# LM60.net
KiCad netlist of a schematic drawn in Altium Designer
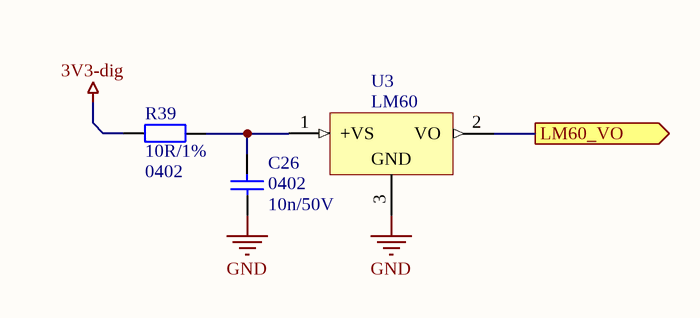
[diagram p0: LM60.SchDoc]

(export (version "E")
  (design (tool "Eeschema 10.0.6"))
  (components
    (comp (ref "C26")
      (value "10n/50V")
      (footprint "SMD_Capacitor_0402")
      (description "Ceramic Cap Murata Automotive 10n/50V X7R 0402")
      (fields
        (field (name "MANUFACTURER") "Murata")
        (field (name "MANUFACTURERPARTNUMBER") "GCM155R71H103KA55D")
        (field (name "PACKAGE") "0402")
      )
      (libsource (lib "capacitors") (part "Cer_GCM155R71H103KA55D"))
    )
    (comp (ref "R39")
      (value "10R/1%")
      (footprint "SMD_Resistor_0402")
      (description "10R/1% Vishay CRCW 0402 Resistor. 63mW, 100ppm, 50V.")
      (fields
        (field (name "MANUFACTURER") "Vishay")
        (field (name "MANUFACTURERPARTNUMBER") "CRCW040210R0FKxxxx")
        (field (name "PACKAGE") "0402")
      )
      (libsource (lib "resistors") (part "CRCW040210R0FKxxxx"))
    )
    (comp (ref "U3")
      (value "LM60")
      (footprint "SOT23-3")
      (description "Analog temperature sensor")
      (libsource (lib "microcircuits") (part "LM60"))
    )
  )
  (nets
    (net (code "1") (name "/LM60_VO") (class "Default")
      (node (ref "U3") (pin "2") (pinfunction "VO_2") (pintype "output"))
    )
    (net (code "2") (name "3V3-dig") (class "Default")
      (node (ref "R39") (pin "1") (pinfunction "1_1") (pintype "passive"))
    )
    (net (code "3") (name "GND") (class "Default")
      (node (ref "C26") (pin "2") (pinfunction "2_2") (pintype "passive"))
      (node (ref "U3") (pin "3") (pinfunction "GND_3") (pintype "power_in"))
    )
    (net (code "4") (name "Net-(U3-+VS)") (class "Default")
      (node (ref "C26") (pin "1") (pinfunction "1_1") (pintype "passive"))
      (node (ref "R39") (pin "2") (pinfunction "2_2") (pintype "passive"))
      (node (ref "U3") (pin "1") (pinfunction "+VS_1") (pintype "input"))
    )
  )
)
